# RTC_Card.net
KiCad netlist of a schematic drawn in EAGLE
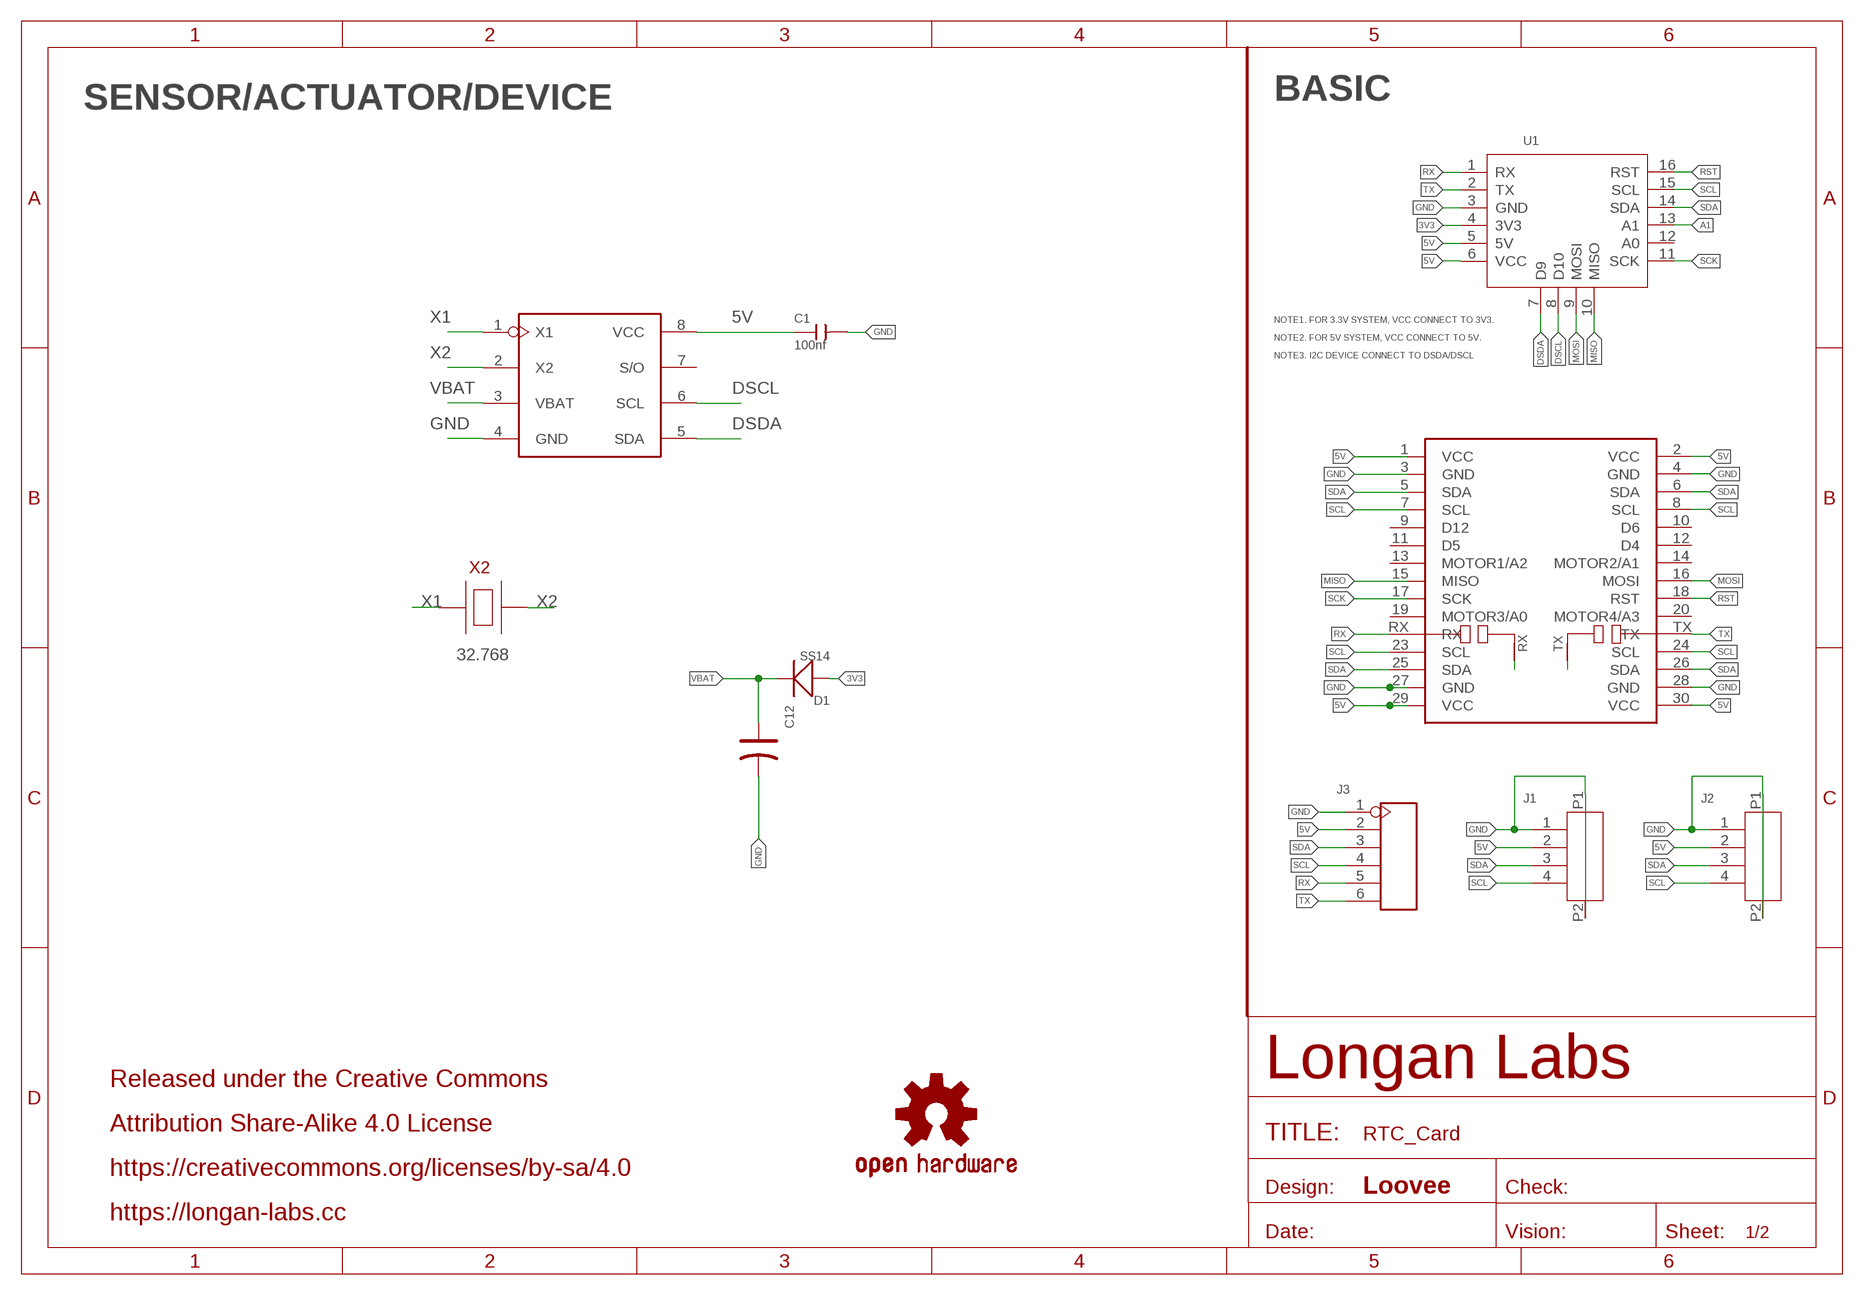
[diagram p0: schematic, sheet 1]

(export (version "E")
  (design (tool "Eeschema 10.0.6"))
  (components
    (comp (ref "C1")
      (value "100nf")
      (footprint "eagle-import:C0603")
      (libsource (lib "eagle-import") (part "CAP-0603"))
    )
    (comp (ref "C12")
      (value "CAP-POLAR-CS-ME-414TA")
      (footprint "eagle-import:SC-2P-D4.8MM")
      (libsource (lib "eagle-import") (part "CAP-POLAR-CS-ME-414TA"))
    )
    (comp (ref "D1")
      (value "SS14")
      (footprint "eagle-import:DO-214AC")
      (libsource (lib "eagle-import") (part "DIODE'SMA'"))
    )
    (comp (ref "J1")
      (value "HEADER-4P-1.0")
      (footprint "eagle-import:4P-1.0-90D")
      (libsource (lib "eagle-import") (part "HEADER-4P-1.0"))
    )
    (comp (ref "J2")
      (value "HEADER-4P-1.0")
      (footprint "eagle-import:4P-1.0-90D")
      (libsource (lib "eagle-import") (part "HEADER-4P-1.0"))
    )
    (comp (ref "J3")
      (value "HEADER-6P-55/35MIL")
      (footprint "eagle-import:H6-2.54")
      (libsource (lib "eagle-import") (part "HEADER-6P-55/35MIL"))
    )
    (comp (ref "LOGO2")
      (value "OSHW-LOGOS")
      (footprint "eagle-import:OSHW-LOGO-S")
      (libsource (lib "eagle-import") (part "OSHW-LOGOS"))
    )
    (comp (ref "MOUDLE2")
      (value "MOUDLE-CARDS-UART'BOARD'")
      (footprint "eagle-import:MOUDLE-2X15P-UART")
      (libsource (lib "eagle-import") (part "MOUDLE-CARDS-UART'BOARD'"))
    )
    (comp (ref "U1")
      (value "MOUDLE-CARDS")
      (footprint "eagle-import:16P-2.0-CARDS")
      (libsource (lib "eagle-import") (part "MOUDLE-CARDS"))
    )
    (comp (ref "U2")
      (value "DS1307")
      (footprint "eagle-import:SO08")
      (libsource (lib "eagle-import") (part "DS1307"))
    )
    (comp (ref "X2")
      (value "32768")
      (footprint "eagle-import:2P-3215")
      (libsource (lib "eagle-import") (part "CRYSTAL-2P"))
    )
  )
  (nets
    (net (code "1") (name "3V3") (class "Default")
      (node (ref "D1") (pin "1") (pinfunction "+_1") (pintype "passive"))
      (node (ref "U1") (pin "4") (pinfunction "3V3_4") (pintype "bidirectional"))
    )
    (net (code "2") (name "5V") (class "Default")
      (node (ref "C1") (pin "1") (pinfunction "1_1") (pintype "passive"))
      (node (ref "J1") (pin "2") (pinfunction "2_2") (pintype "bidirectional"))
      (node (ref "J2") (pin "2") (pinfunction "2_2") (pintype "bidirectional"))
      (node (ref "J3") (pin "2") (pinfunction "2_2") (pintype "bidirectional"))
      (node (ref "MOUDLE2") (pin "1") (pinfunction "VCC_1") (pintype "bidirectional"))
      (node (ref "MOUDLE2") (pin "2") (pinfunction "VCC_2") (pintype "bidirectional"))
      (node (ref "MOUDLE2") (pin "29") (pinfunction "VCC_29") (pintype "bidirectional"))
      (node (ref "MOUDLE2") (pin "30") (pinfunction "VCC_30") (pintype "bidirectional"))
      (node (ref "U1") (pin "5") (pinfunction "5V_5") (pintype "bidirectional"))
      (node (ref "U1") (pin "6") (pinfunction "VCC_6") (pintype "bidirectional"))
      (node (ref "U2") (pin "8") (pinfunction "VCC_8") (pintype "bidirectional"))
    )
    (net (code "3") (name "A1") (class "Default")
      (node (ref "U1") (pin "13") (pinfunction "A1_13") (pintype "bidirectional"))
    )
    (net (code "4") (name "DSCL") (class "Default")
      (node (ref "U1") (pin "8") (pinfunction "D10_8") (pintype "bidirectional"))
      (node (ref "U2") (pin "6") (pinfunction "SCL_6") (pintype "bidirectional"))
    )
    (net (code "5") (name "DSDA") (class "Default")
      (node (ref "U1") (pin "7") (pinfunction "D9_7") (pintype "bidirectional"))
      (node (ref "U2") (pin "5") (pinfunction "SDA_5") (pintype "bidirectional"))
    )
    (net (code "6") (name "GND") (class "Default")
      (node (ref "C1") (pin "2") (pinfunction "2_2") (pintype "passive"))
      (node (ref "C12") (pin "2") (pinfunction "-_2") (pintype "passive"))
      (node (ref "J1") (pin "1") (pinfunction "1_1") (pintype "bidirectional"))
      (node (ref "J1") (pin "P1") (pinfunction "P1_P1") (pintype "bidirectional"))
      (node (ref "J1") (pin "P2") (pinfunction "P2_P2") (pintype "bidirectional"))
      (node (ref "J2") (pin "1") (pinfunction "1_1") (pintype "bidirectional"))
      (node (ref "J2") (pin "P1") (pinfunction "P1_P1") (pintype "bidirectional"))
      (node (ref "J2") (pin "P2") (pinfunction "P2_P2") (pintype "bidirectional"))
      (node (ref "J3") (pin "1") (pinfunction "1_1") (pintype "bidirectional"))
      (node (ref "MOUDLE2") (pin "27") (pinfunction "GND_27") (pintype "bidirectional"))
      (node (ref "MOUDLE2") (pin "28") (pinfunction "GND_28") (pintype "bidirectional"))
      (node (ref "MOUDLE2") (pin "3") (pinfunction "GND_3") (pintype "bidirectional"))
      (node (ref "MOUDLE2") (pin "4") (pinfunction "GND_4") (pintype "bidirectional"))
      (node (ref "U1") (pin "3") (pinfunction "GND_3") (pintype "bidirectional"))
      (node (ref "U2") (pin "4") (pinfunction "GND_4") (pintype "bidirectional"))
    )
    (net (code "7") (name "MISO") (class "Default")
      (node (ref "MOUDLE2") (pin "15") (pinfunction "MISO_15") (pintype "bidirectional"))
      (node (ref "U1") (pin "10") (pinfunction "MISO_10") (pintype "bidirectional"))
    )
    (net (code "8") (name "MOSI") (class "Default")
      (node (ref "MOUDLE2") (pin "16") (pinfunction "MOSI_16") (pintype "bidirectional"))
      (node (ref "U1") (pin "9") (pinfunction "MOSI_9") (pintype "bidirectional"))
    )
    (net (code "9") (name "Net-(MOUDLE2-RX{slash}N-PadRX{slash}N1)") (class "Default")
      (node (ref "MOUDLE2") (pin "RX/N1") (pinfunction "RX/N_RX/N1") (pintype "bidirectional"))
      (node (ref "MOUDLE2") (pin "RX/N2") (pinfunction "RX/N_RX/N2") (pintype "bidirectional"))
    )
    (net (code "10") (name "Net-(MOUDLE2-TX{slash}N-PadTX{slash}N1)") (class "Default")
      (node (ref "MOUDLE2") (pin "TX/N1") (pinfunction "TX/N_TX/N1") (pintype "bidirectional"))
      (node (ref "MOUDLE2") (pin "TX/N2") (pinfunction "TX/N_TX/N2") (pintype "bidirectional"))
    )
    (net (code "11") (name "RST") (class "Default")
      (node (ref "MOUDLE2") (pin "18") (pinfunction "RST_18") (pintype "bidirectional"))
      (node (ref "U1") (pin "16") (pinfunction "RST_16") (pintype "bidirectional"))
    )
    (net (code "12") (name "RX") (class "Default")
      (node (ref "J3") (pin "5") (pinfunction "5_5") (pintype "bidirectional"))
      (node (ref "MOUDLE2") (pin "RX") (pinfunction "RX_RX") (pintype "bidirectional"))
      (node (ref "U1") (pin "1") (pinfunction "RX_1") (pintype "bidirectional"))
    )
    (net (code "13") (name "SCK") (class "Default")
      (node (ref "MOUDLE2") (pin "17") (pinfunction "SCK_17") (pintype "bidirectional"))
      (node (ref "U1") (pin "11") (pinfunction "SCK_11") (pintype "bidirectional"))
    )
    (net (code "14") (name "SCL") (class "Default")
      (node (ref "J1") (pin "4") (pinfunction "4_4") (pintype "bidirectional"))
      (node (ref "J2") (pin "4") (pinfunction "4_4") (pintype "bidirectional"))
      (node (ref "J3") (pin "4") (pinfunction "4_4") (pintype "bidirectional"))
      (node (ref "MOUDLE2") (pin "23") (pinfunction "SCL_23") (pintype "bidirectional"))
      (node (ref "MOUDLE2") (pin "24") (pinfunction "SCL_24") (pintype "bidirectional"))
      (node (ref "MOUDLE2") (pin "7") (pinfunction "SCL_7") (pintype "bidirectional"))
      (node (ref "MOUDLE2") (pin "8") (pinfunction "SCL_8") (pintype "bidirectional"))
      (node (ref "U1") (pin "15") (pinfunction "SCL_15") (pintype "bidirectional"))
    )
    (net (code "15") (name "SDA") (class "Default")
      (node (ref "J1") (pin "3") (pinfunction "3_3") (pintype "bidirectional"))
      (node (ref "J2") (pin "3") (pinfunction "3_3") (pintype "bidirectional"))
      (node (ref "J3") (pin "3") (pinfunction "3_3") (pintype "bidirectional"))
      (node (ref "MOUDLE2") (pin "25") (pinfunction "SDA_25") (pintype "bidirectional"))
      (node (ref "MOUDLE2") (pin "26") (pinfunction "SDA_26") (pintype "bidirectional"))
      (node (ref "MOUDLE2") (pin "5") (pinfunction "SDA_5") (pintype "bidirectional"))
      (node (ref "MOUDLE2") (pin "6") (pinfunction "SDA_6") (pintype "bidirectional"))
      (node (ref "U1") (pin "14") (pinfunction "SDA_14") (pintype "bidirectional"))
    )
    (net (code "16") (name "TX") (class "Default")
      (node (ref "J3") (pin "6") (pinfunction "6_6") (pintype "bidirectional"))
      (node (ref "MOUDLE2") (pin "TX") (pinfunction "TX_TX") (pintype "bidirectional"))
      (node (ref "U1") (pin "2") (pinfunction "TX_2") (pintype "bidirectional"))
    )
    (net (code "17") (name "VBAT") (class "Default")
      (node (ref "C12") (pin "1") (pinfunction "+_1") (pintype "passive"))
      (node (ref "D1") (pin "2") (pinfunction "-_2") (pintype "passive"))
      (node (ref "U2") (pin "3") (pinfunction "VBAT_3") (pintype "bidirectional"))
    )
    (net (code "18") (name "X1") (class "Default")
      (node (ref "U2") (pin "1") (pinfunction "X1_1") (pintype "bidirectional"))
      (node (ref "X2") (pin "X1") (pinfunction "P$1_X1") (pintype "bidirectional"))
    )
    (net (code "19") (name "X2") (class "Default")
      (node (ref "U2") (pin "2") (pinfunction "X2_2") (pintype "bidirectional"))
      (node (ref "X2") (pin "X2") (pinfunction "P$2_X2") (pintype "bidirectional"))
    )
    (net (code "20") (name "unconnected-(MOUDLE2-D4-Pad12)") (class "Default")
      (node (ref "MOUDLE2") (pin "12") (pinfunction "D4_12") (pintype "bidirectional"))
    )
    (net (code "21") (name "unconnected-(MOUDLE2-D5-Pad11)") (class "Default")
      (node (ref "MOUDLE2") (pin "11") (pinfunction "D5_11") (pintype "bidirectional"))
    )
    (net (code "22") (name "unconnected-(MOUDLE2-D6-Pad10)") (class "Default")
      (node (ref "MOUDLE2") (pin "10") (pinfunction "D6_10") (pintype "bidirectional"))
    )
    (net (code "23") (name "unconnected-(MOUDLE2-D12-Pad9)") (class "Default")
      (node (ref "MOUDLE2") (pin "9") (pinfunction "D12_9") (pintype "bidirectional"))
    )
    (net (code "24") (name "unconnected-(MOUDLE2-MOTOR1{slash}A2-Pad13)") (class "Default")
      (node (ref "MOUDLE2") (pin "13") (pinfunction "MOTOR1/A2_13") (pintype "bidirectional"))
    )
    (net (code "25") (name "unconnected-(MOUDLE2-MOTOR2{slash}A1-Pad14)") (class "Default")
      (node (ref "MOUDLE2") (pin "14") (pinfunction "MOTOR2/A1_14") (pintype "bidirectional"))
    )
    (net (code "26") (name "unconnected-(MOUDLE2-MOTOR3{slash}A0-Pad19)") (class "Default")
      (node (ref "MOUDLE2") (pin "19") (pinfunction "MOTOR3/A0_19") (pintype "bidirectional"))
    )
    (net (code "27") (name "unconnected-(MOUDLE2-MOTOR4{slash}A3-Pad20)") (class "Default")
      (node (ref "MOUDLE2") (pin "20") (pinfunction "MOTOR4/A3_20") (pintype "bidirectional"))
    )
    (net (code "28") (name "unconnected-(U1-A0-Pad12)") (class "Default")
      (node (ref "U1") (pin "12") (pinfunction "A0_12") (pintype "bidirectional"))
    )
    (net (code "29") (name "unconnected-(U2-S{slash}O-Pad7)") (class "Default")
      (node (ref "U2") (pin "7") (pinfunction "S/O_7") (pintype "bidirectional"))
    )
  )
)
